# MCU.net
KiCad netlist of a schematic drawn in Altium Designer
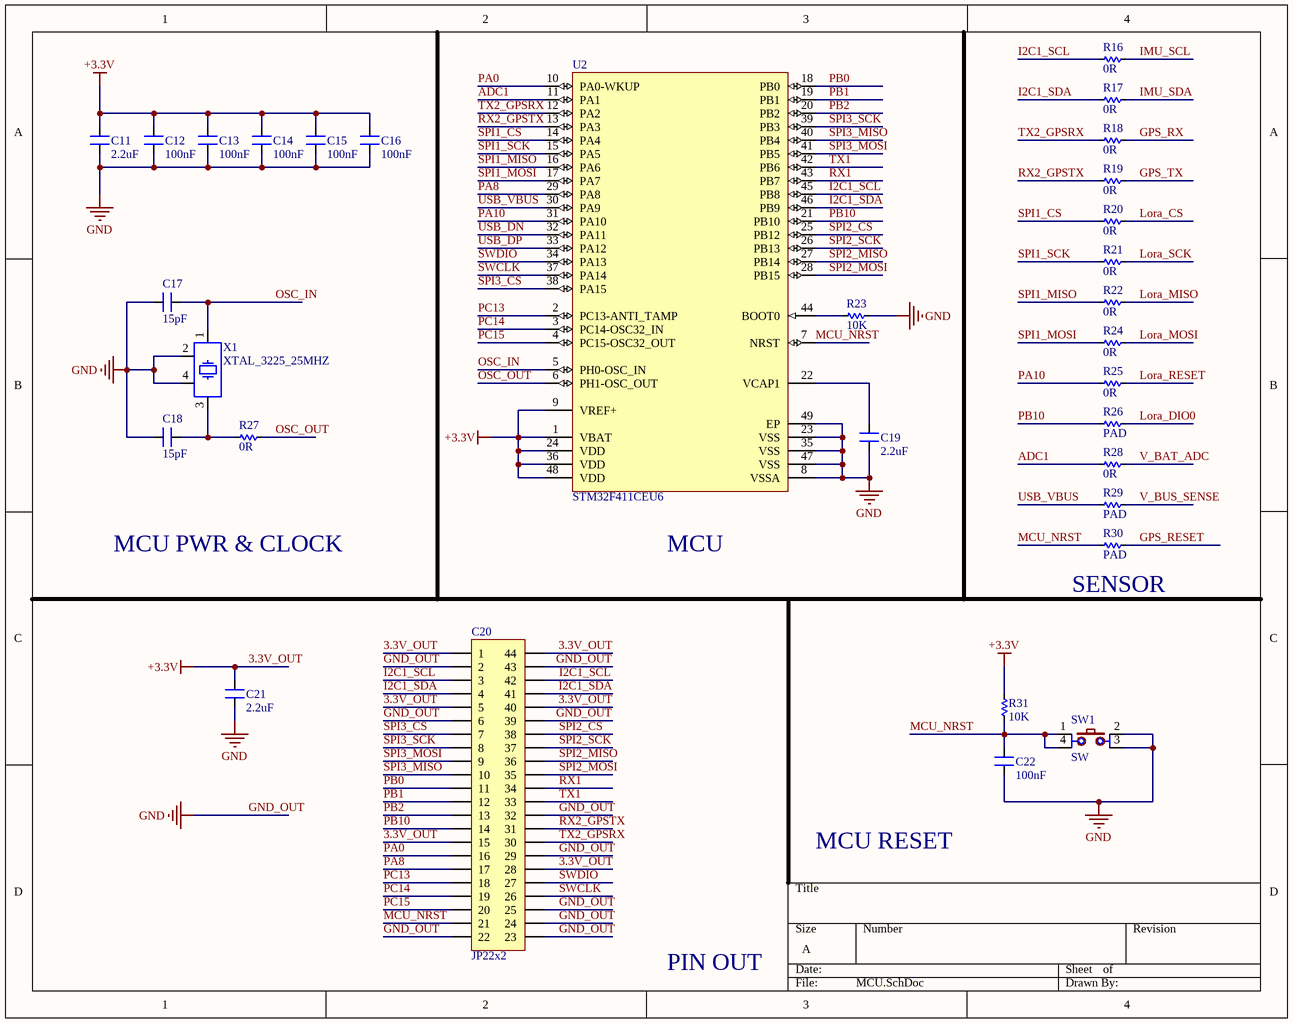
[diagram p0: MCU.SchDoc]

(export (version "E")
  (design (tool "Eeschema 10.0.6"))
  (components
    (comp (ref "C11") (value "2.2uF") (footprint "CN-SMD-0805") (libsource (lib "DATN_LIB") (part "Cap-SMD")))
    (comp (ref "C12") (value "100nF") (footprint "CN-SMD-0603") (libsource (lib "DATN_LIB") (part "Cap-SMD")))
    (comp (ref "C13") (value "100nF") (footprint "CN-SMD-0603") (libsource (lib "DATN_LIB") (part "Cap-SMD")))
    (comp (ref "C14") (value "100nF") (footprint "CN-SMD-0603") (libsource (lib "DATN_LIB") (part "Cap-SMD")))
    (comp (ref "C15") (value "100nF") (footprint "CN-SMD-0603") (libsource (lib "DATN_LIB") (part "Cap-SMD")))
    (comp (ref "C16") (value "100nF") (footprint "CN-SMD-0603") (libsource (lib "DATN_LIB") (part "Cap-SMD")))
    (comp (ref "C17") (value "15pF") (footprint "CN-SMD-0603") (libsource (lib "DATN_LIB") (part "Cap-SMD")))
    (comp (ref "C18") (value "15pF") (footprint "CN-SMD-0603") (libsource (lib "DATN_LIB") (part "Cap-SMD")))
    (comp (ref "C19") (value "2.2uF") (footprint "CN-SMD-0805") (libsource (lib "DATN_LIB") (part "Cap-SMD")))
    (comp (ref "C20")
      (value "JP22x2")
      (footprint "JP22-D2T")
      (description "WR-PHD 2.54 mm Dual Socket Header")
      (fields
        (field (name "MANUFACTURER") "Würth Elektronik eiSos GmbH")
        (field (name "PARTNO") "61304421821")
        (field (name "CREATED BY") "Karrer Zheng")
      )
      (libsource (lib "LIBRARY") (part "JP22x2"))
    )
    (comp (ref "C21") (value "2.2uF") (footprint "CN-SMD-0805") (libsource (lib "DATN_LIB") (part "Cap-SMD")))
    (comp (ref "C22") (value "100nF") (footprint "CN-SMD-0603") (libsource (lib "DATN_LIB") (part "Cap-SMD")))
    (comp (ref "R16")
      (value "0R")
      (footprint "RES-SMD-0603")
      (description "Resistor")
      (fields
        (field (name "MANUFACTURER") "Generic Components")
        (field (name "PUBLISHER") "Altium Hobart Technology Centre")
      )
      (libsource (lib "DATN_LIB") (part "Res-SMD"))
    )
    (comp (ref "R17")
      (value "0R")
      (footprint "RES-SMD-0603")
      (description "Resistor")
      (fields
        (field (name "MANUFACTURER") "Generic Components")
        (field (name "PUBLISHER") "Altium Hobart Technology Centre")
      )
      (libsource (lib "DATN_LIB") (part "Res-SMD"))
    )
    (comp (ref "R18")
      (value "0R")
      (footprint "RES-SMD-0603")
      (description "Resistor")
      (fields
        (field (name "MANUFACTURER") "Generic Components")
        (field (name "PUBLISHER") "Altium Hobart Technology Centre")
      )
      (libsource (lib "DATN_LIB") (part "Res-SMD"))
    )
    (comp (ref "R19")
      (value "0R")
      (footprint "RES-SMD-0603")
      (description "Resistor")
      (fields
        (field (name "MANUFACTURER") "Generic Components")
        (field (name "PUBLISHER") "Altium Hobart Technology Centre")
      )
      (libsource (lib "DATN_LIB") (part "Res-SMD"))
    )
    (comp (ref "R20")
      (value "0R")
      (footprint "RES-SMD-0603")
      (description "Resistor")
      (fields
        (field (name "MANUFACTURER") "Generic Components")
        (field (name "PUBLISHER") "Altium Hobart Technology Centre")
      )
      (libsource (lib "DATN_LIB") (part "Res-SMD"))
    )
    (comp (ref "R21")
      (value "0R")
      (footprint "RES-SMD-0603")
      (description "Resistor")
      (fields
        (field (name "MANUFACTURER") "Generic Components")
        (field (name "PUBLISHER") "Altium Hobart Technology Centre")
      )
      (libsource (lib "DATN_LIB") (part "Res-SMD"))
    )
    (comp (ref "R22")
      (value "0R")
      (footprint "RES-SMD-0603")
      (description "Resistor")
      (fields
        (field (name "MANUFACTURER") "Generic Components")
        (field (name "PUBLISHER") "Altium Hobart Technology Centre")
      )
      (libsource (lib "DATN_LIB") (part "Res-SMD"))
    )
    (comp (ref "R23")
      (value "10K")
      (footprint "RES-SMD-0603")
      (description "Resistor")
      (fields
        (field (name "MANUFACTURER") "Generic Components")
        (field (name "PUBLISHER") "Altium Hobart Technology Centre")
      )
      (libsource (lib "DATN_LIB") (part "Res-SMD"))
    )
    (comp (ref "R24")
      (value "0R")
      (footprint "RES-SMD-0603")
      (description "Resistor")
      (fields
        (field (name "MANUFACTURER") "Generic Components")
        (field (name "PUBLISHER") "Altium Hobart Technology Centre")
      )
      (libsource (lib "DATN_LIB") (part "Res-SMD"))
    )
    (comp (ref "R25")
      (value "0R")
      (footprint "RES-SMD-0603")
      (description "Resistor")
      (fields
        (field (name "MANUFACTURER") "Generic Components")
        (field (name "PUBLISHER") "Altium Hobart Technology Centre")
      )
      (libsource (lib "DATN_LIB") (part "Res-SMD"))
    )
    (comp (ref "R26")
      (value "PAD")
      (footprint "PAD-RES-SMD-0603")
      (description "Resistor")
      (fields
        (field (name "MANUFACTURER") "Generic Components")
        (field (name "PUBLISHER") "Altium Hobart Technology Centre")
      )
      (libsource (lib "DATN_LIB") (part "Res-SMD"))
    )
    (comp (ref "R27")
      (value "0R")
      (footprint "RES-SMD-0603")
      (description "Resistor")
      (fields
        (field (name "MANUFACTURER") "Generic Components")
        (field (name "PUBLISHER") "Altium Hobart Technology Centre")
      )
      (libsource (lib "DATN_LIB") (part "Res-SMD"))
    )
    (comp (ref "R28")
      (value "0R")
      (footprint "RES-SMD-0603")
      (description "Resistor")
      (fields
        (field (name "MANUFACTURER") "Generic Components")
        (field (name "PUBLISHER") "Altium Hobart Technology Centre")
      )
      (libsource (lib "DATN_LIB") (part "Res-SMD"))
    )
    (comp (ref "R29")
      (value "PAD")
      (footprint "PAD-RES-SMD-0603")
      (description "Resistor")
      (fields
        (field (name "MANUFACTURER") "Generic Components")
        (field (name "PUBLISHER") "Altium Hobart Technology Centre")
      )
      (libsource (lib "DATN_LIB") (part "Res-SMD"))
    )
    (comp (ref "R30")
      (value "PAD")
      (footprint "PAD-RES-SMD-0603")
      (description "Resistor")
      (fields
        (field (name "MANUFACTURER") "Generic Components")
        (field (name "PUBLISHER") "Altium Hobart Technology Centre")
      )
      (libsource (lib "DATN_LIB") (part "Res-SMD"))
    )
    (comp (ref "R31")
      (value "10K")
      (footprint "RES-SMD-0603")
      (description "Resistor")
      (fields
        (field (name "MANUFACTURER") "Generic Components")
        (field (name "PUBLISHER") "Altium Hobart Technology Centre")
      )
      (libsource (lib "DATN_LIB") (part "Res-SMD"))
    )
    (comp (ref "SW1")
      (value "SW")
      (footprint "SW2-SMD")
      (description "Switch button 4 pin")
      (libsource (lib "DATN_LIB") (part "SW4"))
    )
    (comp (ref "U2")
      (value "STM32F411CEU6")
      (footprint "STM-UFQFPN48_L")
      (libsource (lib "DATN_LIB") (part "STM32F411CEU6"))
    )
    (comp (ref "X1")
      (value "XTAL_3225_25MHZ")
      (footprint "XTAL_3225")
      (description "Crystal Oscillator")
      (libsource (lib "DATN_LIB") (part "XTAL 4 Pin"))
    )
  )
  (nets
    (net (code "1") (name "+3.3V") (class "Default")
      (node (ref "C11") (pin "2") (pinfunction "2_2") (pintype "passive"))
      (node (ref "C12") (pin "2") (pinfunction "2_2") (pintype "passive"))
      (node (ref "C13") (pin "2") (pinfunction "2_2") (pintype "passive"))
      (node (ref "C14") (pin "2") (pinfunction "2_2") (pintype "passive"))
      (node (ref "C15") (pin "2") (pinfunction "2_2") (pintype "passive"))
      (node (ref "C16") (pin "2") (pinfunction "2_2") (pintype "passive"))
      (node (ref "C20") (pin "1") (pinfunction "1_1") (pintype "passive"))
      (node (ref "C20") (pin "15") (pinfunction "15_15") (pintype "passive"))
      (node (ref "C20") (pin "28") (pinfunction "28_28") (pintype "passive"))
      (node (ref "C20") (pin "40") (pinfunction "40_40") (pintype "passive"))
      (node (ref "C20") (pin "44") (pinfunction "44_44") (pintype "passive"))
      (node (ref "C20") (pin "5") (pinfunction "5_5") (pintype "passive"))
      (node (ref "C21") (pin "2") (pinfunction "2_2") (pintype "passive"))
      (node (ref "R31") (pin "1") (pinfunction "1_1") (pintype "passive"))
      (node (ref "U2") (pin "1") (pinfunction "VBAT_1") (pintype "power_in"))
      (node (ref "U2") (pin "24") (pinfunction "VDD_24") (pintype "power_in"))
      (node (ref "U2") (pin "36") (pinfunction "VDD_36") (pintype "power_in"))
      (node (ref "U2") (pin "48") (pinfunction "VDD_48") (pintype "power_in"))
      (node (ref "U2") (pin "9") (pinfunction "VREF+_9") (pintype "power_in"))
    )
    (net (code "2") (name "/ADC1") (class "Default")
      (node (ref "R28") (pin "1") (pinfunction "1_1") (pintype "passive"))
      (node (ref "U2") (pin "11") (pinfunction "PA1_11") (pintype "bidirectional"))
    )
    (net (code "3") (name "/GPS_RESET") (class "Default")
      (node (ref "R30") (pin "2") (pinfunction "2_2") (pintype "passive"))
    )
    (net (code "4") (name "/GPS_RX") (class "Default")
      (node (ref "R18") (pin "2") (pinfunction "2_2") (pintype "passive"))
    )
    (net (code "5") (name "/GPS_TX") (class "Default")
      (node (ref "R19") (pin "2") (pinfunction "2_2") (pintype "passive"))
    )
    (net (code "6") (name "/I2C1_SCL") (class "Default")
      (node (ref "C20") (pin "3") (pinfunction "3_3") (pintype "passive"))
      (node (ref "C20") (pin "42") (pinfunction "42_42") (pintype "passive"))
      (node (ref "R16") (pin "1") (pinfunction "1_1") (pintype "passive"))
      (node (ref "U2") (pin "45") (pinfunction "PB8_45") (pintype "bidirectional"))
    )
    (net (code "7") (name "/I2C1_SDA") (class "Default")
      (node (ref "C20") (pin "4") (pinfunction "4_4") (pintype "passive"))
      (node (ref "C20") (pin "41") (pinfunction "41_41") (pintype "passive"))
      (node (ref "R17") (pin "1") (pinfunction "1_1") (pintype "passive"))
      (node (ref "U2") (pin "46") (pinfunction "PB9_46") (pintype "bidirectional"))
    )
    (net (code "8") (name "/IMU_SCL") (class "Default")
      (node (ref "R16") (pin "2") (pinfunction "2_2") (pintype "passive"))
    )
    (net (code "9") (name "/IMU_SDA") (class "Default")
      (node (ref "R17") (pin "2") (pinfunction "2_2") (pintype "passive"))
    )
    (net (code "10") (name "/Lora_CS") (class "Default")
      (node (ref "R20") (pin "2") (pinfunction "2_2") (pintype "passive"))
    )
    (net (code "11") (name "/Lora_DIO0") (class "Default")
      (node (ref "R26") (pin "2") (pinfunction "2_2") (pintype "passive"))
    )
    (net (code "12") (name "/Lora_MISO") (class "Default")
      (node (ref "R22") (pin "2") (pinfunction "2_2") (pintype "passive"))
    )
    (net (code "13") (name "/Lora_MOSI") (class "Default")
      (node (ref "R24") (pin "2") (pinfunction "2_2") (pintype "passive"))
    )
    (net (code "14") (name "/Lora_RESET") (class "Default")
      (node (ref "R25") (pin "2") (pinfunction "2_2") (pintype "passive"))
    )
    (net (code "15") (name "/Lora_SCK") (class "Default")
      (node (ref "R21") (pin "2") (pinfunction "2_2") (pintype "passive"))
    )
    (net (code "16") (name "/MCU_NRST") (class "Default")
      (node (ref "C20") (pin "21") (pinfunction "21_21") (pintype "passive"))
      (node (ref "C22") (pin "2") (pinfunction "2_2") (pintype "passive"))
      (node (ref "R30") (pin "1") (pinfunction "1_1") (pintype "passive"))
      (node (ref "R31") (pin "2") (pinfunction "2_2") (pintype "passive"))
      (node (ref "SW1") (pin "1") (pintype "passive"))
      (node (ref "SW1") (pin "4") (pinfunction "4_4") (pintype "passive"))
      (node (ref "U2") (pin "7") (pinfunction "NRST_7") (pintype "bidirectional"))
    )
    (net (code "17") (name "/OSC_IN") (class "Default")
      (node (ref "C17") (pin "1") (pinfunction "1_1") (pintype "passive"))
      (node (ref "U2") (pin "5") (pinfunction "PH0-OSC_IN_5") (pintype "bidirectional"))
      (node (ref "X1") (pin "1") (pinfunction "1_1") (pintype "passive"))
    )
    (net (code "18") (name "/OSC_OUT") (class "Default")
      (node (ref "R27") (pin "2") (pinfunction "2_2") (pintype "passive"))
      (node (ref "U2") (pin "6") (pinfunction "PH1-OSC_OUT_6") (pintype "bidirectional"))
    )
    (net (code "19") (name "/PA0") (class "Default")
      (node (ref "C20") (pin "16") (pinfunction "16_16") (pintype "passive"))
      (node (ref "U2") (pin "10") (pinfunction "PA0-WKUP_10") (pintype "bidirectional"))
    )
    (net (code "20") (name "/PA8") (class "Default")
      (node (ref "C20") (pin "17") (pinfunction "17_17") (pintype "passive"))
      (node (ref "U2") (pin "29") (pinfunction "PA8_29") (pintype "bidirectional"))
    )
    (net (code "21") (name "/PA10") (class "Default")
      (node (ref "R25") (pin "1") (pinfunction "1_1") (pintype "passive"))
      (node (ref "U2") (pin "31") (pinfunction "PA10_31") (pintype "bidirectional"))
    )
    (net (code "22") (name "/PB0") (class "Default")
      (node (ref "C20") (pin "11") (pinfunction "11_11") (pintype "passive"))
      (node (ref "U2") (pin "18") (pinfunction "PB0_18") (pintype "bidirectional"))
    )
    (net (code "23") (name "/PB1") (class "Default")
      (node (ref "C20") (pin "12") (pinfunction "12_12") (pintype "passive"))
      (node (ref "U2") (pin "19") (pinfunction "PB1_19") (pintype "bidirectional"))
    )
    (net (code "24") (name "/PB2") (class "Default")
      (node (ref "C20") (pin "13") (pinfunction "13_13") (pintype "passive"))
      (node (ref "U2") (pin "20") (pinfunction "PB2_20") (pintype "bidirectional"))
    )
    (net (code "25") (name "/PB10") (class "Default")
      (node (ref "C20") (pin "14") (pinfunction "14_14") (pintype "passive"))
      (node (ref "R26") (pin "1") (pinfunction "1_1") (pintype "passive"))
      (node (ref "U2") (pin "21") (pinfunction "PB10_21") (pintype "bidirectional"))
    )
    (net (code "26") (name "/PC13") (class "Default")
      (node (ref "C20") (pin "18") (pinfunction "18_18") (pintype "passive"))
      (node (ref "U2") (pin "2") (pinfunction "PC13-ANTI_TAMP_2") (pintype "bidirectional"))
    )
    (net (code "27") (name "/PC14") (class "Default")
      (node (ref "C20") (pin "19") (pinfunction "19_19") (pintype "passive"))
      (node (ref "U2") (pin "3") (pinfunction "PC14-OSC32_IN_3") (pintype "bidirectional"))
    )
    (net (code "28") (name "/PC15") (class "Default")
      (node (ref "C20") (pin "20") (pinfunction "20_20") (pintype "passive"))
      (node (ref "U2") (pin "4") (pinfunction "PC15-OSC32_OUT_4") (pintype "bidirectional"))
    )
    (net (code "29") (name "/RX1") (class "Default")
      (node (ref "C20") (pin "34") (pinfunction "34_34") (pintype "passive"))
      (node (ref "U2") (pin "43") (pinfunction "PB7_43") (pintype "bidirectional"))
    )
    (net (code "30") (name "/RX2_GPSTX") (class "Default")
      (node (ref "C20") (pin "31") (pinfunction "31_31") (pintype "passive"))
      (node (ref "R19") (pin "1") (pinfunction "1_1") (pintype "passive"))
      (node (ref "U2") (pin "13") (pinfunction "PA3_13") (pintype "bidirectional"))
    )
    (net (code "31") (name "/SPI1_CS") (class "Default")
      (node (ref "R20") (pin "1") (pinfunction "1_1") (pintype "passive"))
      (node (ref "U2") (pin "14") (pinfunction "PA4_14") (pintype "bidirectional"))
    )
    (net (code "32") (name "/SPI1_MISO") (class "Default")
      (node (ref "R22") (pin "1") (pinfunction "1_1") (pintype "passive"))
      (node (ref "U2") (pin "16") (pinfunction "PA6_16") (pintype "bidirectional"))
    )
    (net (code "33") (name "/SPI1_MOSI") (class "Default")
      (node (ref "R24") (pin "1") (pinfunction "1_1") (pintype "passive"))
      (node (ref "U2") (pin "17") (pinfunction "PA7_17") (pintype "bidirectional"))
    )
    (net (code "34") (name "/SPI1_SCK") (class "Default")
      (node (ref "R21") (pin "1") (pinfunction "1_1") (pintype "passive"))
      (node (ref "U2") (pin "15") (pinfunction "PA5_15") (pintype "bidirectional"))
    )
    (net (code "35") (name "/SPI2_CS") (class "Default")
      (node (ref "C20") (pin "38") (pinfunction "38_38") (pintype "passive"))
      (node (ref "U2") (pin "25") (pinfunction "PB12_25") (pintype "bidirectional"))
    )
    (net (code "36") (name "/SPI2_MISO") (class "Default")
      (node (ref "C20") (pin "36") (pinfunction "36_36") (pintype "passive"))
      (node (ref "U2") (pin "27") (pinfunction "PB14_27") (pintype "bidirectional"))
    )
    (net (code "37") (name "/SPI2_MOSI") (class "Default")
      (node (ref "C20") (pin "35") (pinfunction "35_35") (pintype "passive"))
      (node (ref "U2") (pin "28") (pinfunction "PB15_28") (pintype "bidirectional"))
    )
    (net (code "38") (name "/SPI2_SCK") (class "Default")
      (node (ref "C20") (pin "37") (pinfunction "37_37") (pintype "passive"))
      (node (ref "U2") (pin "26") (pinfunction "PB13_26") (pintype "bidirectional"))
    )
    (net (code "39") (name "/SPI3_CS") (class "Default")
      (node (ref "C20") (pin "7") (pinfunction "7_7") (pintype "passive"))
      (node (ref "U2") (pin "38") (pinfunction "PA15_38") (pintype "bidirectional"))
    )
    (net (code "40") (name "/SPI3_MISO") (class "Default")
      (node (ref "C20") (pin "10") (pinfunction "10_10") (pintype "passive"))
      (node (ref "U2") (pin "40") (pinfunction "PB4_40") (pintype "bidirectional"))
    )
    (net (code "41") (name "/SPI3_MOSI") (class "Default")
      (node (ref "C20") (pin "9") (pinfunction "9_9") (pintype "passive"))
      (node (ref "U2") (pin "41") (pinfunction "PB5_41") (pintype "bidirectional"))
    )
    (net (code "42") (name "/SPI3_SCK") (class "Default")
      (node (ref "C20") (pin "8") (pinfunction "8_8") (pintype "passive"))
      (node (ref "U2") (pin "39") (pinfunction "PB3_39") (pintype "bidirectional"))
    )
    (net (code "43") (name "/SWCLK") (class "Default")
      (node (ref "C20") (pin "26") (pinfunction "26_26") (pintype "passive"))
      (node (ref "U2") (pin "37") (pinfunction "PA14_37") (pintype "bidirectional"))
    )
    (net (code "44") (name "/SWDIO") (class "Default")
      (node (ref "C20") (pin "27") (pinfunction "27_27") (pintype "passive"))
      (node (ref "U2") (pin "34") (pinfunction "PA13_34") (pintype "bidirectional"))
    )
    (net (code "45") (name "/TX1") (class "Default")
      (node (ref "C20") (pin "33") (pinfunction "33_33") (pintype "passive"))
      (node (ref "U2") (pin "42") (pinfunction "PB6_42") (pintype "bidirectional"))
    )
    (net (code "46") (name "/TX2_GPSRX") (class "Default")
      (node (ref "C20") (pin "30") (pinfunction "30_30") (pintype "passive"))
      (node (ref "R18") (pin "1") (pinfunction "1_1") (pintype "passive"))
      (node (ref "U2") (pin "12") (pinfunction "PA2_12") (pintype "bidirectional"))
    )
    (net (code "47") (name "/USB_DN") (class "Default")
      (node (ref "U2") (pin "32") (pinfunction "PA11_32") (pintype "bidirectional"))
    )
    (net (code "48") (name "/USB_DP") (class "Default")
      (node (ref "U2") (pin "33") (pinfunction "PA12_33") (pintype "bidirectional"))
    )
    (net (code "49") (name "/USB_VBUS") (class "Default")
      (node (ref "R29") (pin "1") (pinfunction "1_1") (pintype "passive"))
      (node (ref "U2") (pin "30") (pinfunction "PA9_30") (pintype "bidirectional"))
    )
    (net (code "50") (name "/V_BAT_ADC") (class "Default")
      (node (ref "R28") (pin "2") (pinfunction "2_2") (pintype "passive"))
    )
    (net (code "51") (name "/V_BUS_SENSE") (class "Default")
      (node (ref "R29") (pin "2") (pinfunction "2_2") (pintype "passive"))
    )
    (net (code "52") (name "GND") (class "Default")
      (node (ref "C11") (pin "1") (pinfunction "1_1") (pintype "passive"))
      (node (ref "C12") (pin "1") (pinfunction "1_1") (pintype "passive"))
      (node (ref "C13") (pin "1") (pinfunction "1_1") (pintype "passive"))
      (node (ref "C14") (pin "1") (pinfunction "1_1") (pintype "passive"))
      (node (ref "C15") (pin "1") (pinfunction "1_1") (pintype "passive"))
      (node (ref "C16") (pin "1") (pinfunction "1_1") (pintype "passive"))
      (node (ref "C17") (pin "2") (pinfunction "2_2") (pintype "passive"))
      (node (ref "C18") (pin "2") (pinfunction "2_2") (pintype "passive"))
      (node (ref "C19") (pin "1") (pinfunction "1_1") (pintype "passive"))
      (node (ref "C20") (pin "2") (pinfunction "2_2") (pintype "passive"))
      (node (ref "C20") (pin "22") (pinfunction "22_22") (pintype "passive"))
      (node (ref "C20") (pin "23") (pinfunction "23_23") (pintype "passive"))
      (node (ref "C20") (pin "24") (pinfunction "24_24") (pintype "passive"))
      (node (ref "C20") (pin "25") (pinfunction "25_25") (pintype "passive"))
      (node (ref "C20") (pin "29") (pinfunction "29_29") (pintype "passive"))
      (node (ref "C20") (pin "32") (pinfunction "32_32") (pintype "passive"))
      (node (ref "C20") (pin "39") (pinfunction "39_39") (pintype "passive"))
      (node (ref "C20") (pin "43") (pinfunction "43_43") (pintype "passive"))
      (node (ref "C20") (pin "6") (pinfunction "6_6") (pintype "passive"))
      (node (ref "C21") (pin "1") (pinfunction "1_1") (pintype "passive"))
      (node (ref "C22") (pin "1") (pinfunction "1_1") (pintype "passive"))
      (node (ref "R23") (pin "2") (pinfunction "2_2") (pintype "passive"))
      (node (ref "SW1") (pin "2") (pinfunction "2_2") (pintype "passive"))
      (node (ref "SW1") (pin "3") (pinfunction "3_3") (pintype "passive"))
      (node (ref "U2") (pin "23") (pinfunction "VSS_23") (pintype "power_in"))
      (node (ref "U2") (pin "35") (pinfunction "VSS_35") (pintype "power_in"))
      (node (ref "U2") (pin "47") (pinfunction "VSS_47") (pintype "power_in"))
      (node (ref "U2") (pin "49") (pinfunction "EP_49") (pintype "power_in"))
      (node (ref "U2") (pin "8") (pinfunction "VSSA_8") (pintype "power_in"))
      (node (ref "X1") (pin "2") (pinfunction "2_2") (pintype "passive"))
      (node (ref "X1") (pin "4") (pinfunction "4_4") (pintype "passive"))
    )
    (net (code "53") (name "Net-(C18-Pad1)") (class "Default")
      (node (ref "C18") (pin "1") (pinfunction "1_1") (pintype "passive"))
      (node (ref "R27") (pin "1") (pinfunction "1_1") (pintype "passive"))
      (node (ref "X1") (pin "3") (pinfunction "3_3") (pintype "passive"))
    )
    (net (code "54") (name "Net-(U2-BOOT0)") (class "Default")
      (node (ref "R23") (pin "1") (pinfunction "1_1") (pintype "passive"))
      (node (ref "U2") (pin "44") (pinfunction "BOOT0_44") (pintype "input"))
    )
    (net (code "55") (name "Net-(U2-VCAP1)") (class "Default")
      (node (ref "C19") (pin "2") (pinfunction "2_2") (pintype "passive"))
      (node (ref "U2") (pin "22") (pinfunction "VCAP1_22") (pintype "passive"))
    )
  )
)
